# DuinoTag.net
KiCad netlist of a schematic drawn in Altium Designer
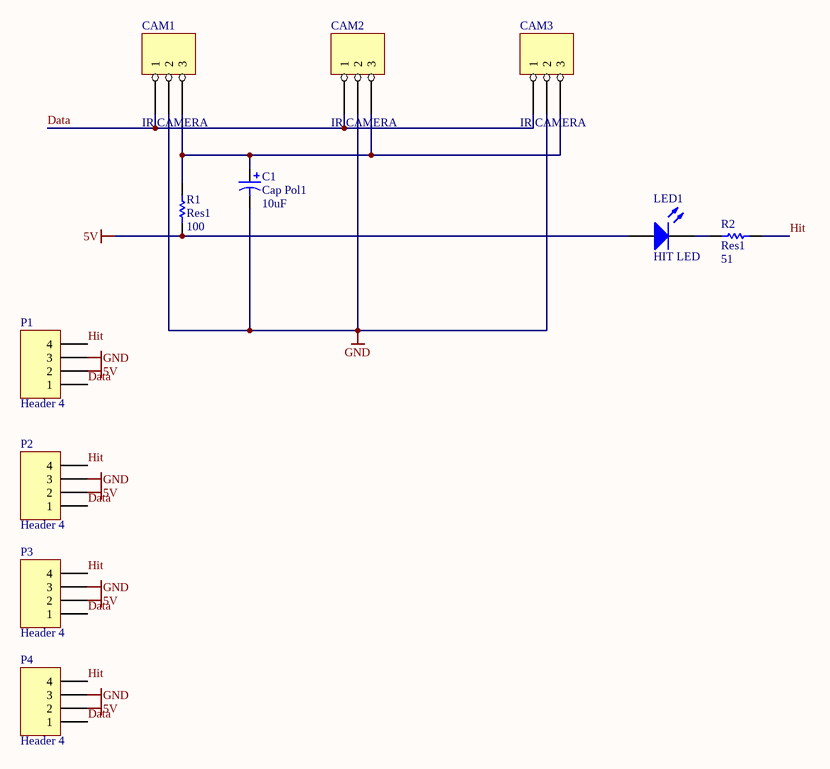
[diagram p0: DuinoTag.SchDoc]

(export (version "E")
  (design (tool "Eeschema 10.0.6"))
  (components
    (comp (ref "C1")
      (value "Cap Pol1")
      (footprint "Vishay Footprints:94SP-C")
      (description "Polarized Capacitor (Radial)")
      (fields (field (name "ALTIUM_VALUE") "10uF") (field (name "PUBLISHER") "Altium Limited"))
      (libsource (lib "Miscellaneous Devices") (part "Cap Pol1"))
    )
    (comp (ref "CAM1")
      (value "IR CAMERA")
      (footprint "SIP3")
      (description "CONN HEADR BRKWAY .100 3POS STR")
      (libsource (lib "raven-parts") (part "HEADER 3"))
    )
    (comp (ref "CAM2")
      (value "IR CAMERA")
      (footprint "SIP3")
      (description "CONN HEADR BRKWAY .100 3POS STR")
      (libsource (lib "raven-parts") (part "HEADER 3"))
    )
    (comp (ref "CAM3")
      (value "IR CAMERA")
      (footprint "SIP3")
      (description "CONN HEADR BRKWAY .100 3POS STR")
      (libsource (lib "raven-parts") (part "HEADER 3"))
    )
    (comp (ref "LED1")
      (value "HIT LED")
      (footprint "WL-TMRC THT LED round mono-color color lens:Type 5mm")
      (description "Typical RED GaAs LED")
      (fields (field (name "PUBLISHER") "Altium Limited"))
      (libsource (lib "Miscellaneous Devices") (part "LED1"))
    )
    (comp (ref "P1")
      (value "Header 4")
      (footprint "HDR1X4")
      (description "Header, 4-Pin")
      (fields (field (name "PUBLISHER") "Altium Limited"))
      (libsource (lib "Miscellaneous Connectors") (part "Header 4"))
    )
    (comp (ref "P2")
      (value "Header 4")
      (footprint "HDR1X4")
      (description "Header, 4-Pin")
      (fields (field (name "PUBLISHER") "Altium Limited"))
      (libsource (lib "Miscellaneous Connectors") (part "Header 4"))
    )
    (comp (ref "P3")
      (value "Header 4")
      (footprint "HDR1X4")
      (description "Header, 4-Pin")
      (fields (field (name "PUBLISHER") "Altium Limited"))
      (libsource (lib "Miscellaneous Connectors") (part "Header 4"))
    )
    (comp (ref "P4")
      (value "Header 4")
      (footprint "HDR1X4")
      (description "Header, 4-Pin")
      (fields (field (name "PUBLISHER") "Altium Limited"))
      (libsource (lib "Miscellaneous Connectors") (part "Header 4"))
    )
    (comp (ref "R1")
      (value "Res1")
      (footprint "AXIAL-0.3")
      (description "Resistor")
      (fields (field (name "ALTIUM_VALUE") "100") (field (name "PUBLISHER") "Altium Limited"))
      (libsource (lib "Miscellaneous Devices") (part "Res1"))
    )
    (comp (ref "R2")
      (value "Res1")
      (footprint "AXIAL-0.3")
      (description "Resistor")
      (fields (field (name "ALTIUM_VALUE") "51") (field (name "PUBLISHER") "Altium Limited"))
      (libsource (lib "Miscellaneous Devices") (part "Res1"))
    )
  )
  (nets
    (net (code "1") (name "/Data") (class "Default")
      (node (ref "CAM1") (pin "1") (pinfunction "1_1") (pintype "passive"))
      (node (ref "CAM2") (pin "1") (pinfunction "1_1") (pintype "passive"))
      (node (ref "CAM3") (pin "1") (pinfunction "1_1") (pintype "passive"))
      (node (ref "P1") (pin "1") (pinfunction "1_1") (pintype "passive"))
      (node (ref "P2") (pin "1") (pinfunction "1_1") (pintype "passive"))
      (node (ref "P3") (pin "1") (pinfunction "1_1") (pintype "passive"))
      (node (ref "P4") (pin "1") (pinfunction "1_1") (pintype "passive"))
    )
    (net (code "2") (name "/Hit") (class "Default")
      (node (ref "P1") (pin "4") (pinfunction "4_4") (pintype "passive"))
      (node (ref "P2") (pin "4") (pinfunction "4_4") (pintype "passive"))
      (node (ref "P3") (pin "4") (pinfunction "4_4") (pintype "passive"))
      (node (ref "P4") (pin "4") (pinfunction "4_4") (pintype "passive"))
      (node (ref "R2") (pin "1") (pinfunction "1_1") (pintype "passive"))
    )
    (net (code "3") (name "5V") (class "Default")
      (node (ref "LED1") (pin "1") (pinfunction "A_1") (pintype "passive"))
      (node (ref "P1") (pin "2") (pinfunction "2_2") (pintype "passive"))
      (node (ref "P2") (pin "2") (pinfunction "2_2") (pintype "passive"))
      (node (ref "P3") (pin "2") (pinfunction "2_2") (pintype "passive"))
      (node (ref "P4") (pin "2") (pinfunction "2_2") (pintype "passive"))
      (node (ref "R1") (pin "1") (pinfunction "1_1") (pintype "passive"))
    )
    (net (code "4") (name "GND") (class "Default")
      (node (ref "C1") (pin "2") (pinfunction "2_2") (pintype "passive"))
      (node (ref "CAM1") (pin "2") (pinfunction "2_2") (pintype "passive"))
      (node (ref "CAM2") (pin "2") (pinfunction "2_2") (pintype "passive"))
      (node (ref "CAM3") (pin "2") (pinfunction "2_2") (pintype "passive"))
      (node (ref "P1") (pin "3") (pinfunction "3_3") (pintype "passive"))
      (node (ref "P2") (pin "3") (pinfunction "3_3") (pintype "passive"))
      (node (ref "P3") (pin "3") (pinfunction "3_3") (pintype "passive"))
      (node (ref "P4") (pin "3") (pinfunction "3_3") (pintype "passive"))
    )
    (net (code "5") (name "Net-(C1-Pad1)") (class "Default")
      (node (ref "C1") (pin "1") (pinfunction "1_1") (pintype "passive"))
      (node (ref "CAM1") (pin "3") (pinfunction "3_3") (pintype "passive"))
      (node (ref "CAM2") (pin "3") (pinfunction "3_3") (pintype "passive"))
      (node (ref "CAM3") (pin "3") (pinfunction "3_3") (pintype "passive"))
      (node (ref "R1") (pin "2") (pinfunction "2_2") (pintype "passive"))
    )
    (net (code "6") (name "Net-(LED1-K)") (class "Default")
      (node (ref "LED1") (pin "2") (pinfunction "K_2") (pintype "passive"))
      (node (ref "R2") (pin "2") (pinfunction "2_2") (pintype "passive"))
    )
  )
)
